# easyeda2.net
KiCad netlist of a schematic drawn in EasyEDA
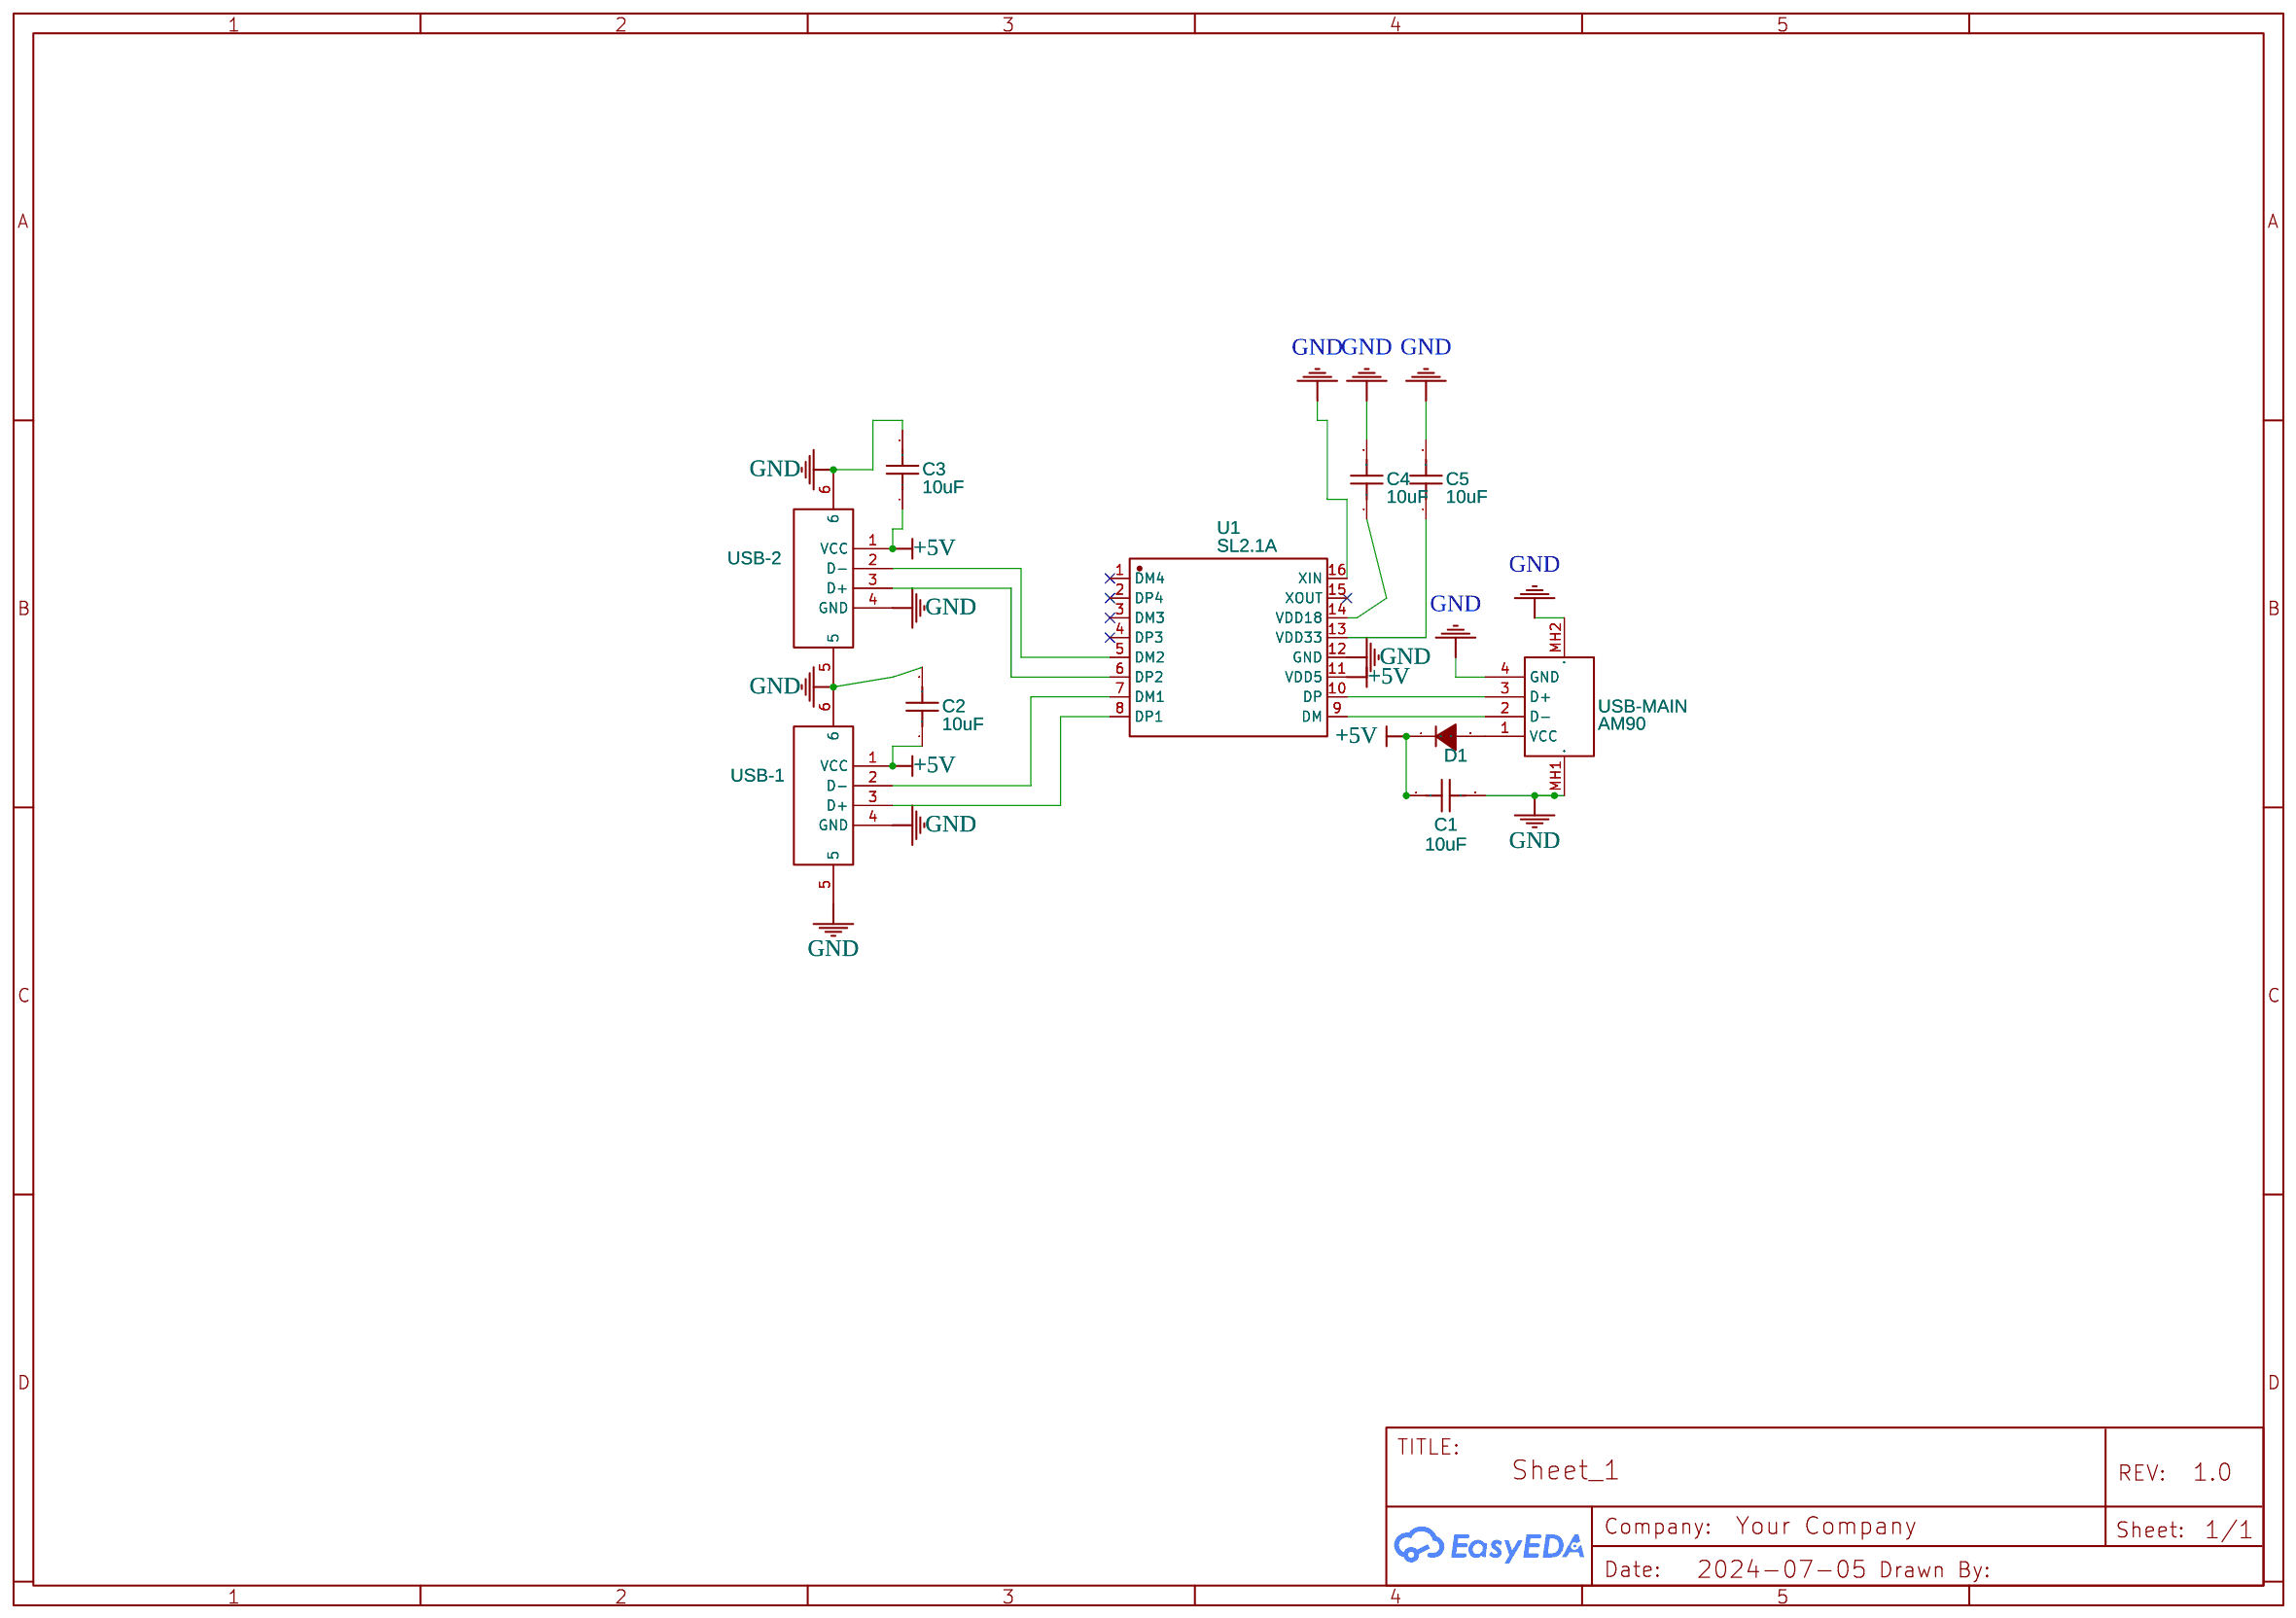
[diagram p0: schematic sheet]

(export (version "E")
  (design (tool "Eeschema 10.0.6"))
  (components
    (comp (ref "C1")
      (value "10uF")
      (fields
        (field (name "Manufacturer Part") "CL10A106KP8NNNC")
        (field (name "Manufacturer") "SAMSUNG(三星)")
      )
      (libsource (lib "") (part "CL10A106KP8NNNC_1"))
    )
    (comp (ref "C2")
      (value "10uF")
      (fields
        (field (name "Manufacturer Part") "CL10A106KP8NNNC")
        (field (name "Manufacturer") "SAMSUNG(三星)")
      )
      (libsource (lib "") (part "CL10A106KP8NNNC"))
    )
    (comp (ref "C3")
      (value "10uF")
      (fields
        (field (name "Manufacturer Part") "CL10A106KP8NNNC")
        (field (name "Manufacturer") "SAMSUNG(三星)")
      )
      (libsource (lib "") (part "CL10A106KP8NNNC"))
    )
    (comp (ref "C4")
      (value "10uF")
      (fields
        (field (name "Manufacturer Part") "CL10A106KP8NNNC")
        (field (name "Manufacturer") "SAMSUNG(三星)")
      )
      (libsource (lib "") (part "CL10A106KP8NNNC"))
    )
    (comp (ref "C5")
      (value "10uF")
      (fields
        (field (name "Manufacturer Part") "CL10A106KP8NNNC")
        (field (name "Manufacturer") "SAMSUNG(三星)")
      )
      (libsource (lib "") (part "CL10A106KP8NNNC"))
    )
    (comp (ref "D1")
      (value "NSR0320MW2T1G")
      (fields (field (name "Manufacturer") "onsemi(安森美)"))
      (libsource (lib "") (part "NSR0320MW2T1G"))
    )
    (comp (ref "U1")
      (value "SL2.1A")
      (fields (field (name "Manufacturer") "CoreChips(和芯润德)"))
      (libsource (lib "") (part "SL2.1A"))
    )
    (comp (ref "USB-1")
      (value "USB-AF-90-14.4X13.6-H7.0-DIP")
      (fields (field (name "Manufacturer Part") "903-131A1011D10100") (field (name "Manufacturer") "精拓金"))
      (libsource (lib "") (part "USB-AF-90-14.4X13.6-H7.0-DIP"))
    )
    (comp (ref "USB-2")
      (value "USB-AF-90-14.4X13.6-H7.0-DIP")
      (fields (field (name "Manufacturer Part") "903-131A1011D10100") (field (name "Manufacturer") "精拓金"))
      (libsource (lib "") (part "USB-AF-90-14.4X13.6-H7.0-DIP"))
    )
    (comp (ref "USB-MAIN")
      (value "AM90")
      (fields (field (name "Manufacturer") "SHOU HAN(首韩)"))
      (libsource (lib "") (part "AM90"))
    )
  )
  (nets
    (net (code "1") (name "+5V") (class "Default")
      (node (ref "C1") (pin "1") (pinfunction "1_1") (pintype "unspecified"))
      (node (ref "C2") (pin "1") (pinfunction "1_1") (pintype "unspecified"))
      (node (ref "C3") (pin "1") (pinfunction "1_1") (pintype "unspecified"))
      (node (ref "D1") (pin "1") (pinfunction "C_1") (pintype "unspecified"))
      (node (ref "U1") (pin "11") (pinfunction "VDD5_11") (pintype "unspecified"))
      (node (ref "USB-1") (pin "1") (pinfunction "VCC_1") (pintype "unspecified"))
      (node (ref "USB-2") (pin "1") (pinfunction "VCC_1") (pintype "unspecified"))
    )
    (net (code "2") (name "GND") (class "Default")
      (node (ref "C1") (pin "2") (pinfunction "2_2") (pintype "unspecified"))
      (node (ref "C2") (pin "2") (pinfunction "2_2") (pintype "unspecified"))
      (node (ref "C3") (pin "2") (pinfunction "2_2") (pintype "unspecified"))
      (node (ref "C4") (pin "2") (pinfunction "2_2") (pintype "unspecified"))
      (node (ref "C5") (pin "2") (pinfunction "2_2") (pintype "unspecified"))
      (node (ref "U1") (pin "12") (pinfunction "GND_12") (pintype "unspecified"))
      (node (ref "U1") (pin "16") (pinfunction "XIN_16") (pintype "unspecified"))
      (node (ref "USB-1") (pin "4") (pinfunction "GND_4") (pintype "unspecified"))
      (node (ref "USB-1") (pin "5") (pinfunction "5_5") (pintype "unspecified"))
      (node (ref "USB-1") (pin "6") (pinfunction "6_6") (pintype "unspecified"))
      (node (ref "USB-2") (pin "4") (pinfunction "GND_4") (pintype "unspecified"))
      (node (ref "USB-2") (pin "5") (pinfunction "5_5") (pintype "unspecified"))
      (node (ref "USB-2") (pin "6") (pinfunction "6_6") (pintype "unspecified"))
      (node (ref "USB-MAIN") (pin "4") (pinfunction "GND_4") (pintype "input"))
      (node (ref "USB-MAIN") (pin "MH1") (pinfunction "MH1_MH1") (pintype "unspecified"))
      (node (ref "USB-MAIN") (pin "MH2") (pinfunction "MH2_MH2") (pintype "unspecified"))
    )
    (net (code "3") (name "Net-(D1-A)") (class "Default")
      (node (ref "D1") (pin "2") (pinfunction "A_2") (pintype "unspecified"))
      (node (ref "USB-MAIN") (pin "1") (pinfunction "VCC_1") (pintype "input"))
    )
    (net (code "4") (name "Net-(U1-DM)") (class "Default")
      (node (ref "U1") (pin "9") (pinfunction "DM_9") (pintype "unspecified"))
      (node (ref "USB-MAIN") (pin "2") (pinfunction "D-_2") (pintype "input"))
    )
    (net (code "5") (name "Net-(U1-DM1)") (class "Default")
      (node (ref "U1") (pin "7") (pinfunction "DM1_7") (pintype "unspecified"))
      (node (ref "USB-1") (pin "2") (pinfunction "D-_2") (pintype "unspecified"))
    )
    (net (code "6") (name "Net-(U1-DM2)") (class "Default")
      (node (ref "U1") (pin "5") (pinfunction "DM2_5") (pintype "unspecified"))
      (node (ref "USB-2") (pin "2") (pinfunction "D-_2") (pintype "unspecified"))
    )
    (net (code "7") (name "Net-(U1-DP)") (class "Default")
      (node (ref "U1") (pin "10") (pinfunction "DP_10") (pintype "unspecified"))
      (node (ref "USB-MAIN") (pin "3") (pinfunction "D+_3") (pintype "input"))
    )
    (net (code "8") (name "Net-(U1-DP1)") (class "Default")
      (node (ref "U1") (pin "8") (pinfunction "DP1_8") (pintype "unspecified"))
      (node (ref "USB-1") (pin "3") (pinfunction "D+_3") (pintype "unspecified"))
    )
    (net (code "9") (name "Net-(U1-DP2)") (class "Default")
      (node (ref "U1") (pin "6") (pinfunction "DP2_6") (pintype "unspecified"))
      (node (ref "USB-2") (pin "3") (pinfunction "D+_3") (pintype "unspecified"))
    )
    (net (code "10") (name "Net-(U1-VDD18)") (class "Default")
      (node (ref "C4") (pin "1") (pinfunction "1_1") (pintype "unspecified"))
      (node (ref "U1") (pin "14") (pinfunction "VDD18_14") (pintype "unspecified"))
    )
    (net (code "11") (name "Net-(U1-VDD33)") (class "Default")
      (node (ref "C5") (pin "1") (pinfunction "1_1") (pintype "unspecified"))
      (node (ref "U1") (pin "13") (pinfunction "VDD33_13") (pintype "unspecified"))
    )
    (net (code "12") (name "unconnected-(U1-DM3-Pad3)") (class "Default")
      (node (ref "U1") (pin "3") (pinfunction "DM3_3") (pintype "unspecified+no_connect"))
    )
    (net (code "13") (name "unconnected-(U1-DM4-Pad1)") (class "Default")
      (node (ref "U1") (pin "1") (pinfunction "DM4_1") (pintype "unspecified+no_connect"))
    )
    (net (code "14") (name "unconnected-(U1-DP3-Pad4)") (class "Default")
      (node (ref "U1") (pin "4") (pinfunction "DP3_4") (pintype "unspecified+no_connect"))
    )
    (net (code "15") (name "unconnected-(U1-DP4-Pad2)") (class "Default")
      (node (ref "U1") (pin "2") (pinfunction "DP4_2") (pintype "unspecified+no_connect"))
    )
    (net (code "16") (name "unconnected-(U1-XOUT-Pad15)") (class "Default")
      (node (ref "U1") (pin "15") (pinfunction "XOUT_15") (pintype "unspecified+no_connect"))
    )
  )
)
